# 4x_tmc5160.net
KiCad netlist of a schematic drawn in Altium Designer
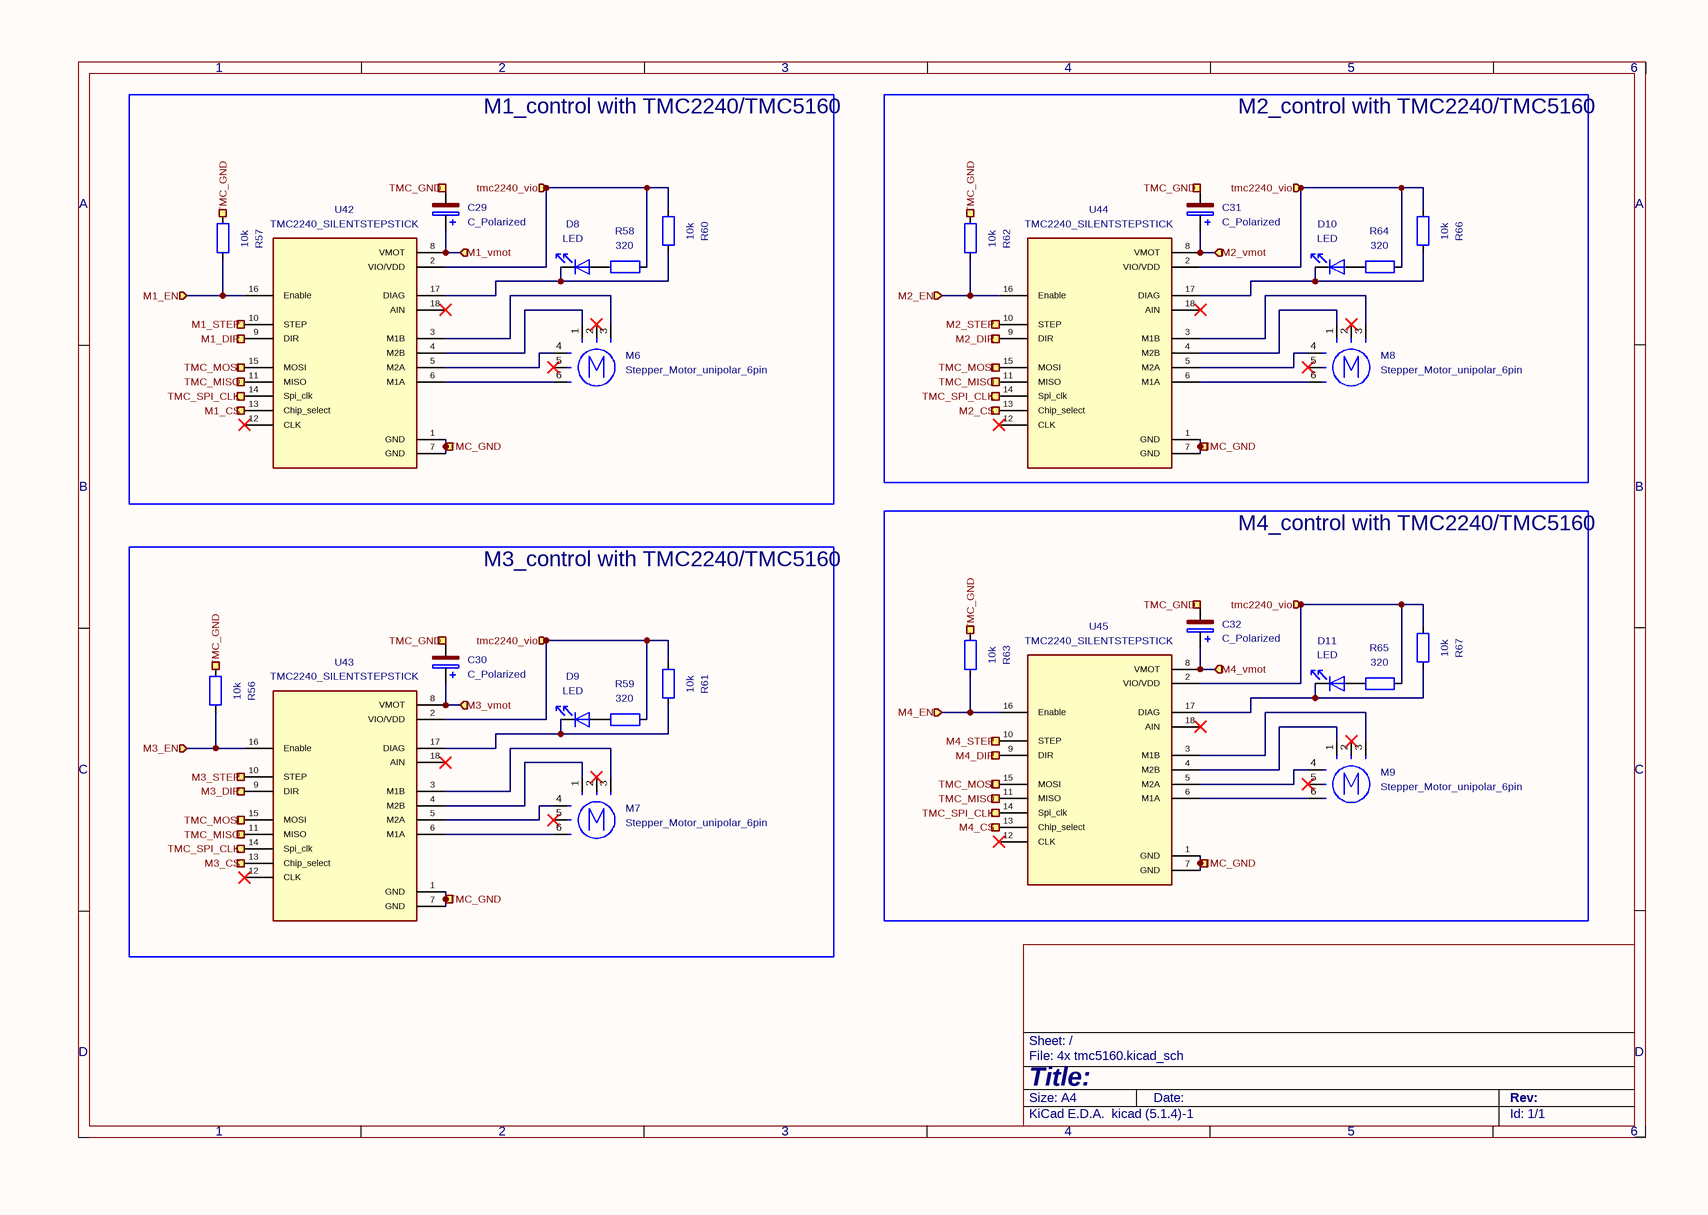
[diagram p0: 4x tmc5160.SchDoc]

(export (version "E")
  (design (tool "Eeschema 10.0.6"))
  (components
    (comp (ref "C29") (value "C_Polarized") (libsource (lib "Device") (part "C_Polarized")))
    (comp (ref "C30") (value "C_Polarized") (libsource (lib "Device") (part "C_Polarized")))
    (comp (ref "C31") (value "C_Polarized") (libsource (lib "Device") (part "C_Polarized")))
    (comp (ref "C32") (value "C_Polarized") (libsource (lib "Device") (part "C_Polarized")))
    (comp (ref "D8") (value "LED") (libsource (lib "Device") (part "LED")))
    (comp (ref "D9") (value "LED") (libsource (lib "Device") (part "LED")))
    (comp (ref "D10") (value "LED") (libsource (lib "Device") (part "LED")))
    (comp (ref "D11") (value "LED") (libsource (lib "Device") (part "LED")))
    (comp (ref "M6")
      (value "Stepper_Motor_unipolar_6pin")
      (libsource (lib "Motor") (part "Stepper_Motor_unipolar_6pin"))
    )
    (comp (ref "M7")
      (value "Stepper_Motor_unipolar_6pin")
      (libsource (lib "Motor") (part "Stepper_Motor_unipolar_6pin"))
    )
    (comp (ref "M8")
      (value "Stepper_Motor_unipolar_6pin")
      (libsource (lib "Motor") (part "Stepper_Motor_unipolar_6pin"))
    )
    (comp (ref "M9")
      (value "Stepper_Motor_unipolar_6pin")
      (libsource (lib "Motor") (part "Stepper_Motor_unipolar_6pin"))
    )
    (comp (ref "R56") (value "10k") (libsource (lib "Device") (part "R")))
    (comp (ref "R57") (value "10k") (libsource (lib "Device") (part "R")))
    (comp (ref "R58") (value "320") (libsource (lib "Device") (part "R")))
    (comp (ref "R59") (value "320") (libsource (lib "Device") (part "R")))
    (comp (ref "R60") (value "10k") (libsource (lib "Device") (part "R")))
    (comp (ref "R61") (value "10k") (libsource (lib "Device") (part "R")))
    (comp (ref "R62") (value "10k") (libsource (lib "Device") (part "R")))
    (comp (ref "R63") (value "10k") (libsource (lib "Device") (part "R")))
    (comp (ref "R64") (value "320") (libsource (lib "Device") (part "R")))
    (comp (ref "R65") (value "320") (libsource (lib "Device") (part "R")))
    (comp (ref "R66") (value "10k") (libsource (lib "Device") (part "R")))
    (comp (ref "R67") (value "10k") (libsource (lib "Device") (part "R")))
    (comp (ref "U42")
      (value "TMC2240_SILENTSTEPSTICK")
      (footprint "MODULE_TMC2209_SILENTSTEPSTICK")
      (fields
        (field (name "MF") "Trinamic Motion Control GmbH")
        (field (name "MP") "TMC2209 SILENTSTEPSTICK")
      )
      (libsource (lib "tmc5060") (part "TMC2209_SILENTSTEPSTICK"))
    )
    (comp (ref "U43")
      (value "TMC2240_SILENTSTEPSTICK")
      (footprint "MODULE_TMC2209_SILENTSTEPSTICK")
      (fields
        (field (name "MF") "Trinamic Motion Control GmbH")
        (field (name "MP") "TMC2209 SILENTSTEPSTICK")
      )
      (libsource (lib "tmc5060") (part "TMC2209_SILENTSTEPSTICK"))
    )
    (comp (ref "U44")
      (value "TMC2240_SILENTSTEPSTICK")
      (footprint "MODULE_TMC2209_SILENTSTEPSTICK")
      (fields
        (field (name "MF") "Trinamic Motion Control GmbH")
        (field (name "MP") "TMC2209 SILENTSTEPSTICK")
      )
      (libsource (lib "tmc5060") (part "TMC2209_SILENTSTEPSTICK"))
    )
    (comp (ref "U45")
      (value "TMC2240_SILENTSTEPSTICK")
      (footprint "MODULE_TMC2209_SILENTSTEPSTICK")
      (fields
        (field (name "MF") "Trinamic Motion Control GmbH")
        (field (name "MP") "TMC2209 SILENTSTEPSTICK")
      )
      (libsource (lib "tmc5060") (part "TMC2209_SILENTSTEPSTICK"))
    )
  )
  (nets
    (net (code "1") (name "/M1_CS") (class "Default")
      (node (ref "U42") (pin "13") (pinfunction "Chip_select_13") (pintype "passive"))
    )
    (net (code "2") (name "/M1_DIR") (class "Default")
      (node (ref "U42") (pin "9") (pinfunction "DIR_9") (pintype "passive"))
    )
    (net (code "3") (name "/M1_EN") (class "Default")
      (node (ref "R57") (pin "1") (pinfunction "1_1") (pintype "passive"))
      (node (ref "U42") (pin "16") (pinfunction "Enable_16") (pintype "passive"))
    )
    (net (code "4") (name "/M1_STEP") (class "Default")
      (node (ref "U42") (pin "10") (pinfunction "STEP_10") (pintype "passive"))
    )
    (net (code "5") (name "/M1_vmot") (class "Default")
      (node (ref "C29") (pin "1") (pinfunction "1_1") (pintype "passive"))
      (node (ref "U42") (pin "8") (pinfunction "VMOT_8") (pintype "passive"))
    )
    (net (code "6") (name "/M2_CS") (class "Default")
      (node (ref "U44") (pin "13") (pinfunction "Chip_select_13") (pintype "passive"))
    )
    (net (code "7") (name "/M2_DIR") (class "Default")
      (node (ref "U44") (pin "9") (pinfunction "DIR_9") (pintype "passive"))
    )
    (net (code "8") (name "/M2_EN") (class "Default")
      (node (ref "R62") (pin "1") (pinfunction "1_1") (pintype "passive"))
      (node (ref "U44") (pin "16") (pinfunction "Enable_16") (pintype "passive"))
    )
    (net (code "9") (name "/M2_STEP") (class "Default")
      (node (ref "U44") (pin "10") (pinfunction "STEP_10") (pintype "passive"))
    )
    (net (code "10") (name "/M2_vmot") (class "Default")
      (node (ref "C31") (pin "1") (pinfunction "1_1") (pintype "passive"))
      (node (ref "U44") (pin "8") (pinfunction "VMOT_8") (pintype "passive"))
    )
    (net (code "11") (name "/M3_CS") (class "Default")
      (node (ref "U43") (pin "13") (pinfunction "Chip_select_13") (pintype "passive"))
    )
    (net (code "12") (name "/M3_DIR") (class "Default")
      (node (ref "U43") (pin "9") (pinfunction "DIR_9") (pintype "passive"))
    )
    (net (code "13") (name "/M3_EN") (class "Default")
      (node (ref "R56") (pin "1") (pinfunction "1_1") (pintype "passive"))
      (node (ref "U43") (pin "16") (pinfunction "Enable_16") (pintype "passive"))
    )
    (net (code "14") (name "/M3_STEP") (class "Default")
      (node (ref "U43") (pin "10") (pinfunction "STEP_10") (pintype "passive"))
    )
    (net (code "15") (name "/M3_vmot") (class "Default")
      (node (ref "C30") (pin "1") (pinfunction "1_1") (pintype "passive"))
      (node (ref "U43") (pin "8") (pinfunction "VMOT_8") (pintype "passive"))
    )
    (net (code "16") (name "/M4_CS") (class "Default")
      (node (ref "U45") (pin "13") (pinfunction "Chip_select_13") (pintype "passive"))
    )
    (net (code "17") (name "/M4_DIR") (class "Default")
      (node (ref "U45") (pin "9") (pinfunction "DIR_9") (pintype "passive"))
    )
    (net (code "18") (name "/M4_EN") (class "Default")
      (node (ref "R63") (pin "1") (pinfunction "1_1") (pintype "passive"))
      (node (ref "U45") (pin "16") (pinfunction "Enable_16") (pintype "passive"))
    )
    (net (code "19") (name "/M4_STEP") (class "Default")
      (node (ref "U45") (pin "10") (pinfunction "STEP_10") (pintype "passive"))
    )
    (net (code "20") (name "/M4_vmot") (class "Default")
      (node (ref "C32") (pin "1") (pinfunction "1_1") (pintype "passive"))
      (node (ref "U45") (pin "8") (pinfunction "VMOT_8") (pintype "passive"))
    )
    (net (code "21") (name "/TMC_GND") (class "Default")
      (node (ref "C29") (pin "2") (pinfunction "2_2") (pintype "passive"))
      (node (ref "C30") (pin "2") (pinfunction "2_2") (pintype "passive"))
      (node (ref "C31") (pin "2") (pinfunction "2_2") (pintype "passive"))
      (node (ref "C32") (pin "2") (pinfunction "2_2") (pintype "passive"))
      (node (ref "R56") (pin "2") (pinfunction "2_2") (pintype "passive"))
      (node (ref "R57") (pin "2") (pinfunction "2_2") (pintype "passive"))
      (node (ref "R62") (pin "2") (pinfunction "2_2") (pintype "passive"))
      (node (ref "R63") (pin "2") (pinfunction "2_2") (pintype "passive"))
      (node (ref "U42") (pin "1") (pinfunction "GND_1") (pintype "passive"))
      (node (ref "U42") (pin "7") (pinfunction "GND_7") (pintype "passive"))
      (node (ref "U43") (pin "1") (pinfunction "GND_1") (pintype "passive"))
      (node (ref "U43") (pin "7") (pinfunction "GND_7") (pintype "passive"))
      (node (ref "U44") (pin "1") (pinfunction "GND_1") (pintype "passive"))
      (node (ref "U44") (pin "7") (pinfunction "GND_7") (pintype "passive"))
      (node (ref "U45") (pin "1") (pinfunction "GND_1") (pintype "passive"))
      (node (ref "U45") (pin "7") (pinfunction "GND_7") (pintype "passive"))
    )
    (net (code "22") (name "/TMC_MISO") (class "Default")
      (node (ref "U42") (pin "11") (pinfunction "MISO_11") (pintype "passive"))
      (node (ref "U43") (pin "11") (pinfunction "MISO_11") (pintype "passive"))
      (node (ref "U44") (pin "11") (pinfunction "MISO_11") (pintype "passive"))
      (node (ref "U45") (pin "11") (pinfunction "MISO_11") (pintype "passive"))
    )
    (net (code "23") (name "/TMC_MOSI") (class "Default")
      (node (ref "U42") (pin "15") (pinfunction "MOSI_15") (pintype "passive"))
      (node (ref "U43") (pin "15") (pinfunction "MOSI_15") (pintype "passive"))
      (node (ref "U44") (pin "15") (pinfunction "MOSI_15") (pintype "passive"))
      (node (ref "U45") (pin "15") (pinfunction "MOSI_15") (pintype "passive"))
    )
    (net (code "24") (name "/TMC_SPI_CLK") (class "Default")
      (node (ref "U42") (pin "14") (pinfunction "Spi_clk_14") (pintype "passive"))
      (node (ref "U43") (pin "14") (pinfunction "Spi_clk_14") (pintype "passive"))
      (node (ref "U44") (pin "14") (pinfunction "Spi_clk_14") (pintype "passive"))
      (node (ref "U45") (pin "14") (pinfunction "Spi_clk_14") (pintype "passive"))
    )
    (net (code "25") (name "/tmc2240_vio") (class "Default")
      (node (ref "R58") (pin "2") (pinfunction "2_2") (pintype "passive"))
      (node (ref "R59") (pin "2") (pinfunction "2_2") (pintype "passive"))
      (node (ref "R60") (pin "2") (pinfunction "2_2") (pintype "passive"))
      (node (ref "R61") (pin "2") (pinfunction "2_2") (pintype "passive"))
      (node (ref "R64") (pin "2") (pinfunction "2_2") (pintype "passive"))
      (node (ref "R65") (pin "2") (pinfunction "2_2") (pintype "passive"))
      (node (ref "R66") (pin "2") (pinfunction "2_2") (pintype "passive"))
      (node (ref "R67") (pin "2") (pinfunction "2_2") (pintype "passive"))
      (node (ref "U42") (pin "2") (pinfunction "VIO/VDD_2") (pintype "passive"))
      (node (ref "U43") (pin "2") (pinfunction "VIO/VDD_2") (pintype "passive"))
      (node (ref "U44") (pin "2") (pinfunction "VIO/VDD_2") (pintype "passive"))
      (node (ref "U45") (pin "2") (pinfunction "VIO/VDD_2") (pintype "passive"))
    )
    (net (code "26") (name "Net-(D8-A)") (class "Default")
      (node (ref "D8") (pin "2") (pinfunction "A_2") (pintype "passive"))
      (node (ref "R58") (pin "1") (pinfunction "1_1") (pintype "passive"))
    )
    (net (code "27") (name "Net-(D8-K)") (class "Default")
      (node (ref "D8") (pin "1") (pinfunction "K_1") (pintype "passive"))
      (node (ref "R60") (pin "1") (pinfunction "1_1") (pintype "passive"))
      (node (ref "U42") (pin "17") (pinfunction "DIAG_17") (pintype "passive"))
    )
    (net (code "28") (name "Net-(D9-A)") (class "Default")
      (node (ref "D9") (pin "2") (pinfunction "A_2") (pintype "passive"))
      (node (ref "R59") (pin "1") (pinfunction "1_1") (pintype "passive"))
    )
    (net (code "29") (name "Net-(D9-K)") (class "Default")
      (node (ref "D9") (pin "1") (pinfunction "K_1") (pintype "passive"))
      (node (ref "R61") (pin "1") (pinfunction "1_1") (pintype "passive"))
      (node (ref "U43") (pin "17") (pinfunction "DIAG_17") (pintype "passive"))
    )
    (net (code "30") (name "Net-(D10-A)") (class "Default")
      (node (ref "D10") (pin "2") (pinfunction "A_2") (pintype "passive"))
      (node (ref "R64") (pin "1") (pinfunction "1_1") (pintype "passive"))
    )
    (net (code "31") (name "Net-(D10-K)") (class "Default")
      (node (ref "D10") (pin "1") (pinfunction "K_1") (pintype "passive"))
      (node (ref "R66") (pin "1") (pinfunction "1_1") (pintype "passive"))
      (node (ref "U44") (pin "17") (pinfunction "DIAG_17") (pintype "passive"))
    )
    (net (code "32") (name "Net-(D11-A)") (class "Default")
      (node (ref "D11") (pin "2") (pinfunction "A_2") (pintype "passive"))
      (node (ref "R65") (pin "1") (pinfunction "1_1") (pintype "passive"))
    )
    (net (code "33") (name "Net-(D11-K)") (class "Default")
      (node (ref "D11") (pin "1") (pinfunction "K_1") (pintype "passive"))
      (node (ref "R67") (pin "1") (pinfunction "1_1") (pintype "passive"))
      (node (ref "U45") (pin "17") (pinfunction "DIAG_17") (pintype "passive"))
    )
    (net (code "34") (name "Net-(M6--)") (class "Default")
      (node (ref "M6") (pin "3") (pinfunction "-_3") (pintype "passive"))
      (node (ref "U42") (pin "3") (pinfunction "M1B_3") (pintype "passive"))
    )
    (net (code "35") (name "Net-(M7--)") (class "Default")
      (node (ref "M7") (pin "3") (pinfunction "-_3") (pintype "passive"))
      (node (ref "U43") (pin "3") (pinfunction "M1B_3") (pintype "passive"))
    )
    (net (code "36") (name "Net-(M8--)") (class "Default")
      (node (ref "M8") (pin "3") (pinfunction "-_3") (pintype "passive"))
      (node (ref "U44") (pin "3") (pinfunction "M1B_3") (pintype "passive"))
    )
    (net (code "37") (name "Net-(M9--)") (class "Default")
      (node (ref "M9") (pin "3") (pinfunction "-_3") (pintype "passive"))
      (node (ref "U45") (pin "3") (pinfunction "M1B_3") (pintype "passive"))
    )
    (net (code "38") (name "Net-(U42-M1A)") (class "Default")
      (node (ref "M6") (pin "6") (pinfunction "6_6") (pintype "passive"))
      (node (ref "U42") (pin "6") (pinfunction "M1A_6") (pintype "passive"))
    )
    (net (code "39") (name "Net-(U42-M2A)") (class "Default")
      (node (ref "M6") (pin "4") (pinfunction "4_4") (pintype "passive"))
      (node (ref "U42") (pin "5") (pinfunction "M2A_5") (pintype "passive"))
    )
    (net (code "40") (name "Net-(U42-M2B)") (class "Default")
      (node (ref "M6") (pin "1") (pinfunction "1_1") (pintype "passive"))
      (node (ref "U42") (pin "4") (pinfunction "M2B_4") (pintype "passive"))
    )
    (net (code "41") (name "Net-(U43-M1A)") (class "Default")
      (node (ref "M7") (pin "6") (pinfunction "6_6") (pintype "passive"))
      (node (ref "U43") (pin "6") (pinfunction "M1A_6") (pintype "passive"))
    )
    (net (code "42") (name "Net-(U43-M2A)") (class "Default")
      (node (ref "M7") (pin "4") (pinfunction "4_4") (pintype "passive"))
      (node (ref "U43") (pin "5") (pinfunction "M2A_5") (pintype "passive"))
    )
    (net (code "43") (name "Net-(U43-M2B)") (class "Default")
      (node (ref "M7") (pin "1") (pinfunction "1_1") (pintype "passive"))
      (node (ref "U43") (pin "4") (pinfunction "M2B_4") (pintype "passive"))
    )
    (net (code "44") (name "Net-(U44-M1A)") (class "Default")
      (node (ref "M8") (pin "6") (pinfunction "6_6") (pintype "passive"))
      (node (ref "U44") (pin "6") (pinfunction "M1A_6") (pintype "passive"))
    )
    (net (code "45") (name "Net-(U44-M2A)") (class "Default")
      (node (ref "M8") (pin "4") (pinfunction "4_4") (pintype "passive"))
      (node (ref "U44") (pin "5") (pinfunction "M2A_5") (pintype "passive"))
    )
    (net (code "46") (name "Net-(U44-M2B)") (class "Default")
      (node (ref "M8") (pin "1") (pinfunction "1_1") (pintype "passive"))
      (node (ref "U44") (pin "4") (pinfunction "M2B_4") (pintype "passive"))
    )
    (net (code "47") (name "Net-(U45-M1A)") (class "Default")
      (node (ref "M9") (pin "6") (pinfunction "6_6") (pintype "passive"))
      (node (ref "U45") (pin "6") (pinfunction "M1A_6") (pintype "passive"))
    )
    (net (code "48") (name "Net-(U45-M2A)") (class "Default")
      (node (ref "M9") (pin "4") (pinfunction "4_4") (pintype "passive"))
      (node (ref "U45") (pin "5") (pinfunction "M2A_5") (pintype "passive"))
    )
    (net (code "49") (name "Net-(U45-M2B)") (class "Default")
      (node (ref "M9") (pin "1") (pinfunction "1_1") (pintype "passive"))
      (node (ref "U45") (pin "4") (pinfunction "M2B_4") (pintype "passive"))
    )
    (net (code "50") (name "unconnected-(M6-Pad2)") (class "Default")
      (node (ref "M6") (pin "2") (pinfunction "2_2") (pintype "passive+no_connect"))
    )
    (net (code "51") (name "unconnected-(M6-Pad5)") (class "Default")
      (node (ref "M6") (pin "5") (pinfunction "5_5") (pintype "passive+no_connect"))
    )
    (net (code "52") (name "unconnected-(M7-Pad2)") (class "Default")
      (node (ref "M7") (pin "2") (pinfunction "2_2") (pintype "passive+no_connect"))
    )
    (net (code "53") (name "unconnected-(M7-Pad5)") (class "Default")
      (node (ref "M7") (pin "5") (pinfunction "5_5") (pintype "passive+no_connect"))
    )
    (net (code "54") (name "unconnected-(M8-Pad2)") (class "Default")
      (node (ref "M8") (pin "2") (pinfunction "2_2") (pintype "passive+no_connect"))
    )
    (net (code "55") (name "unconnected-(M8-Pad5)") (class "Default")
      (node (ref "M8") (pin "5") (pinfunction "5_5") (pintype "passive+no_connect"))
    )
    (net (code "56") (name "unconnected-(M9-Pad2)") (class "Default")
      (node (ref "M9") (pin "2") (pinfunction "2_2") (pintype "passive+no_connect"))
    )
    (net (code "57") (name "unconnected-(M9-Pad5)") (class "Default")
      (node (ref "M9") (pin "5") (pinfunction "5_5") (pintype "passive+no_connect"))
    )
    (net (code "58") (name "unconnected-(U42-AIN-Pad18)") (class "Default")
      (node (ref "U42") (pin "18") (pinfunction "AIN_18") (pintype "passive+no_connect"))
    )
    (net (code "59") (name "unconnected-(U42-CLK-Pad12)") (class "Default")
      (node (ref "U42") (pin "12") (pinfunction "CLK_12") (pintype "passive+no_connect"))
    )
    (net (code "60") (name "unconnected-(U43-AIN-Pad18)") (class "Default")
      (node (ref "U43") (pin "18") (pinfunction "AIN_18") (pintype "passive+no_connect"))
    )
    (net (code "61") (name "unconnected-(U43-CLK-Pad12)") (class "Default")
      (node (ref "U43") (pin "12") (pinfunction "CLK_12") (pintype "passive+no_connect"))
    )
    (net (code "62") (name "unconnected-(U44-AIN-Pad18)") (class "Default")
      (node (ref "U44") (pin "18") (pinfunction "AIN_18") (pintype "passive+no_connect"))
    )
    (net (code "63") (name "unconnected-(U44-CLK-Pad12)") (class "Default")
      (node (ref "U44") (pin "12") (pinfunction "CLK_12") (pintype "passive+no_connect"))
    )
    (net (code "64") (name "unconnected-(U45-AIN-Pad18)") (class "Default")
      (node (ref "U45") (pin "18") (pinfunction "AIN_18") (pintype "passive+no_connect"))
    )
    (net (code "65") (name "unconnected-(U45-CLK-Pad12)") (class "Default")
      (node (ref "U45") (pin "12") (pinfunction "CLK_12") (pintype "passive+no_connect"))
    )
  )
)
